# Wheatstone_Bridge.net
KiCad netlist of a schematic drawn in EAGLE
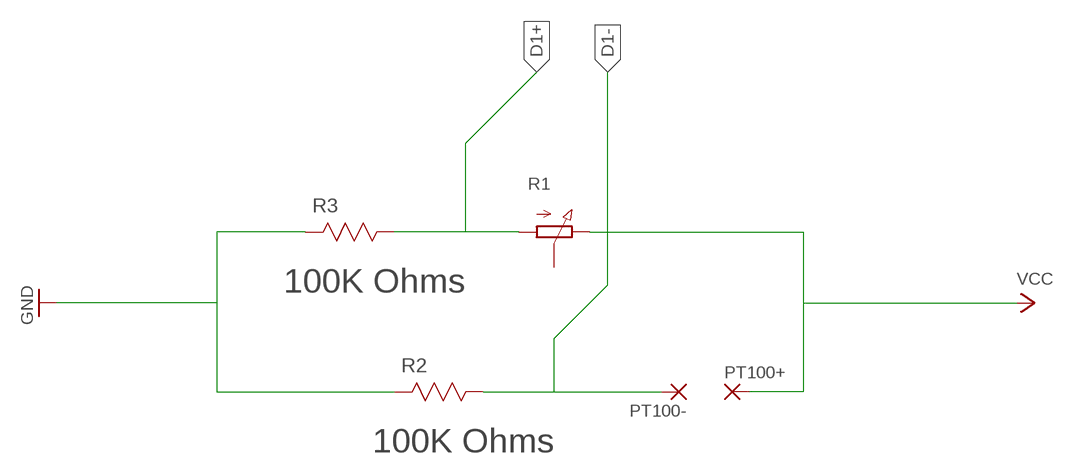
[diagram p0: schematic, sheet 1]

(export (version "E")
  (design (tool "Eeschema 10.0.6"))
  (components
    (comp (ref "PT100+")
      (value "3,17/1,3")
      (footprint "eagle-import:3,17_1,3")
      (libsource (lib "eagle-import") (part "3,17/1,3"))
    )
    (comp (ref "PT100-")
      (value "3,17/1,3")
      (footprint "eagle-import:3,17_1,3")
      (libsource (lib "eagle-import") (part "3,17/1,3"))
    )
    (comp (ref "R1")
      (value "PC25")
      (footprint "eagle-import:PC25")
      (fields (field (name "MF") "CLAROSTAT") (field (name "MPN") "308NPC25KS"))
      (libsource (lib "eagle-import") (part "PC25"))
    )
    (comp (ref "R2")
      (value "100K Ohms")
      (footprint "eagle-import:RESC2013X65N")
      (fields (field (name "MPN") "PNM0805E1003BST5") (field (name "TOLERANCE") "± 0.1 %"))
      (libsource (lib "eagle-import") (part "PNM0805E1003BST5"))
    )
    (comp (ref "R3")
      (value "100K Ohms")
      (footprint "eagle-import:RESC2013X65N")
      (fields (field (name "MPN") "PNM0805E1003BST5") (field (name "TOLERANCE") "± 0.1 %"))
      (libsource (lib "eagle-import") (part "PNM0805E1003BST5"))
    )
  )
  (nets
    (net (code "1") (name "D1+") (class "Default")
      (node (ref "R1") (pin "A") (pinfunction "A_A") (pintype "passive"))
      (node (ref "R3") (pin "1") (pinfunction "1_1") (pintype "passive"))
    )
    (net (code "2") (name "D1-") (class "Default")
      (node (ref "PT100-") (pin "1") (pinfunction "P_1") (pintype "passive"))
      (node (ref "R2") (pin "1") (pinfunction "1_1") (pintype "passive"))
    )
    (net (code "3") (name "GND") (class "Default")
      (node (ref "R2") (pin "2") (pinfunction "2_2") (pintype "passive"))
      (node (ref "R3") (pin "2") (pinfunction "2_2") (pintype "passive"))
    )
    (net (code "4") (name "VCC") (class "Default")
      (node (ref "PT100+") (pin "1") (pinfunction "P_1") (pintype "passive"))
      (node (ref "R1") (pin "E") (pinfunction "E_E") (pintype "passive"))
    )
    (net (code "5") (name "unconnected-(R1-PadS)") (class "Default")
      (node (ref "R1") (pin "S") (pinfunction "S_S") (pintype "passive"))
    )
  )
)
